# PowerBoard.net
KiCad netlist of a schematic drawn in EAGLE
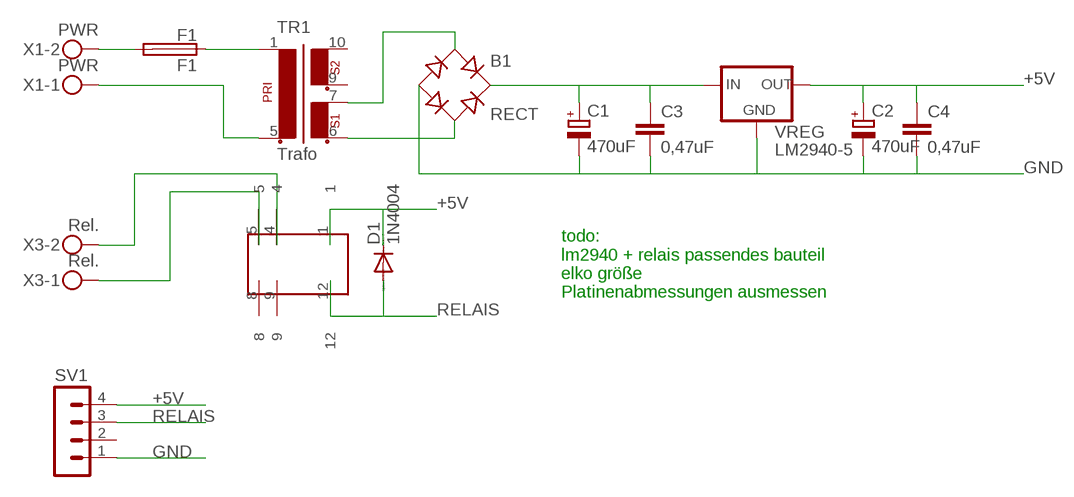
[diagram p0: schematic, sheet 1]

(export (version "E")
  (design (tool "Eeschema 10.0.6"))
  (components
    (comp (ref "B1")
      (value "RECT")
      (footprint "eagle-import:1KAB")
      (libsource (lib "eagle-import") (part "RECTIFIER-1KAB"))
    )
    (comp (ref "C1")
      (value "470uF")
      (footprint "eagle-import:E5-6")
      (libsource (lib "eagle-import") (part "CPOL-EUE5-6"))
    )
    (comp (ref "C2")
      (value "470uF")
      (footprint "eagle-import:E5-6")
      (libsource (lib "eagle-import") (part "CPOL-EUE5-6"))
    )
    (comp (ref "C3")
      (value "0,47uF")
      (footprint "eagle-import:C025-030X050")
      (libsource (lib "eagle-import") (part "C-EU025-030X050"))
    )
    (comp (ref "C4")
      (value "0,47uF")
      (footprint "eagle-import:C025-030X050")
      (libsource (lib "eagle-import") (part "C-EU025-030X050"))
    )
    (comp (ref "D1")
      (value "1N4004")
      (footprint "eagle-import:DO41-10")
      (libsource (lib "eagle-import") (part "1N4004"))
    )
    (comp (ref "F1")
      (value "F1")
      (footprint "eagle-import:FUSE_HOLDER_5X20MM")
      (libsource (lib "eagle-import") (part "FUSEBLANK_5X20MM"))
    )
    (comp (ref "SV1")
      (value "MA04-1")
      (footprint "eagle-import:MA04-1")
      (libsource (lib "eagle-import") (part "MA04-1"))
    )
    (comp (ref "TR1")
      (value "Trafo")
      (footprint "eagle-import:EI30-2")
      (libsource (lib "eagle-import") (part "EI30-2"))
    )
    (comp (ref "U$1")
      (value "V23079-A")
      (footprint "eagle-import:V23079-A")
      (libsource (lib "eagle-import") (part "V23079-A"))
    )
    (comp (ref "VREG")
      (value "LM2940-5")
      (footprint "eagle-import:78MXXS")
      (libsource (lib "eagle-import") (part "78MXXS"))
    )
    (comp (ref "X1")
      (value "PWR")
      (footprint "eagle-import:MKDSN1,5_2-5,08")
      (libsource (lib "eagle-import") (part "MKDSN1,5/2-5,08"))
    )
    (comp (ref "X3")
      (value "Rel.")
      (footprint "eagle-import:MKDSN1,5_2-5,08")
      (libsource (lib "eagle-import") (part "MKDSN1,5/2-5,08"))
    )
  )
  (nets
    (net (code "1") (name "/+5V") (class "Default")
      (node (ref "C2") (pin "+") (pinfunction "+_+") (pintype "passive"))
      (node (ref "C4") (pin "1") (pinfunction "1_1") (pintype "passive"))
      (node (ref "D1") (pin "C") (pinfunction "C_C") (pintype "passive"))
      (node (ref "SV1") (pin "4") (pinfunction "4_4") (pintype "passive"))
      (node (ref "U$1") (pin "1") (pinfunction "1_1") (pintype "bidirectional"))
      (node (ref "VREG") (pin "OUT") (pinfunction "OUT_OUT") (pintype "passive"))
    )
    (net (code "2") (name "/GND") (class "Default")
      (node (ref "B1") (pin "-") (pinfunction "-_-") (pintype "passive"))
      (node (ref "C1") (pin "-") (pinfunction "-_-") (pintype "passive"))
      (node (ref "C2") (pin "-") (pinfunction "-_-") (pintype "passive"))
      (node (ref "C3") (pin "2") (pinfunction "2_2") (pintype "passive"))
      (node (ref "C4") (pin "2") (pinfunction "2_2") (pintype "passive"))
      (node (ref "SV1") (pin "1") (pinfunction "1_1") (pintype "passive"))
      (node (ref "VREG") (pin "GND") (pinfunction "GND_GND") (pintype "input"))
    )
    (net (code "3") (name "/RELAIS") (class "Default")
      (node (ref "D1") (pin "A") (pinfunction "A_A") (pintype "passive"))
      (node (ref "SV1") (pin "3") (pinfunction "3_3") (pintype "passive"))
      (node (ref "U$1") (pin "12") (pinfunction "12_12") (pintype "bidirectional"))
    )
    (net (code "4") (name "Net-(B1-Pad+)") (class "Default")
      (node (ref "B1") (pin "+") (pinfunction "+_+") (pintype "passive"))
      (node (ref "C1") (pin "+") (pinfunction "+_+") (pintype "passive"))
      (node (ref "C3") (pin "1") (pinfunction "1_1") (pintype "passive"))
      (node (ref "VREG") (pin "IN") (pinfunction "IN_IN") (pintype "input"))
    )
    (net (code "5") (name "Net-(F1-Pad1)") (class "Default")
      (node (ref "F1") (pin "1") (pinfunction "1_1") (pintype "passive"))
      (node (ref "TR1") (pin "1") (pinfunction "1_1") (pintype "passive"))
    )
    (net (code "6") (name "Net-(TR1-2)") (class "Default")
      (node (ref "TR1") (pin "5") (pinfunction "2_5") (pintype "passive"))
      (node (ref "X1") (pin "1") (pinfunction "KL_1") (pintype "passive"))
    )
    (net (code "7") (name "Net-(TR1-3)") (class "Default")
      (node (ref "B1") (pin "AC2") (pinfunction "AC2_AC2") (pintype "passive"))
      (node (ref "TR1") (pin "6") (pinfunction "3_6") (pintype "passive"))
    )
    (net (code "8") (name "Net-(TR1-4)") (class "Default")
      (node (ref "B1") (pin "AC1") (pinfunction "AC1_AC1") (pintype "passive"))
      (node (ref "TR1") (pin "7") (pinfunction "4_7") (pintype "passive"))
    )
    (net (code "9") (name "Net-(X1B-KL)") (class "Default")
      (node (ref "F1") (pin "2") (pinfunction "2_2") (pintype "passive"))
      (node (ref "X1") (pin "2") (pinfunction "KL_2") (pintype "passive"))
    )
    (net (code "10") (name "Net-(X3A-KL)") (class "Default")
      (node (ref "U$1") (pin "5") (pinfunction "5_5") (pintype "bidirectional"))
      (node (ref "X3") (pin "1") (pinfunction "KL_1") (pintype "passive"))
    )
    (net (code "11") (name "Net-(X3B-KL)") (class "Default")
      (node (ref "U$1") (pin "4") (pinfunction "4_4") (pintype "bidirectional"))
      (node (ref "X3") (pin "2") (pinfunction "KL_2") (pintype "passive"))
    )
    (net (code "12") (name "unconnected-(SV1-Pad2)") (class "Default")
      (node (ref "SV1") (pin "2") (pinfunction "2_2") (pintype "passive"))
    )
    (net (code "13") (name "unconnected-(TR1-5-Pad9)") (class "Default")
      (node (ref "TR1") (pin "9") (pinfunction "5_9") (pintype "passive"))
    )
    (net (code "14") (name "unconnected-(TR1-6-Pad10)") (class "Default")
      (node (ref "TR1") (pin "10") (pinfunction "6_10") (pintype "passive"))
    )
    (net (code "15") (name "unconnected-(U$1-Pad8)") (class "Default")
      (node (ref "U$1") (pin "8") (pinfunction "8_8") (pintype "bidirectional"))
    )
    (net (code "16") (name "unconnected-(U$1-Pad9)") (class "Default")
      (node (ref "U$1") (pin "9") (pinfunction "9_9") (pintype "bidirectional"))
    )
  )
)
